# ATmega32u4_Example.net
KiCad netlist of a schematic drawn in EAGLE
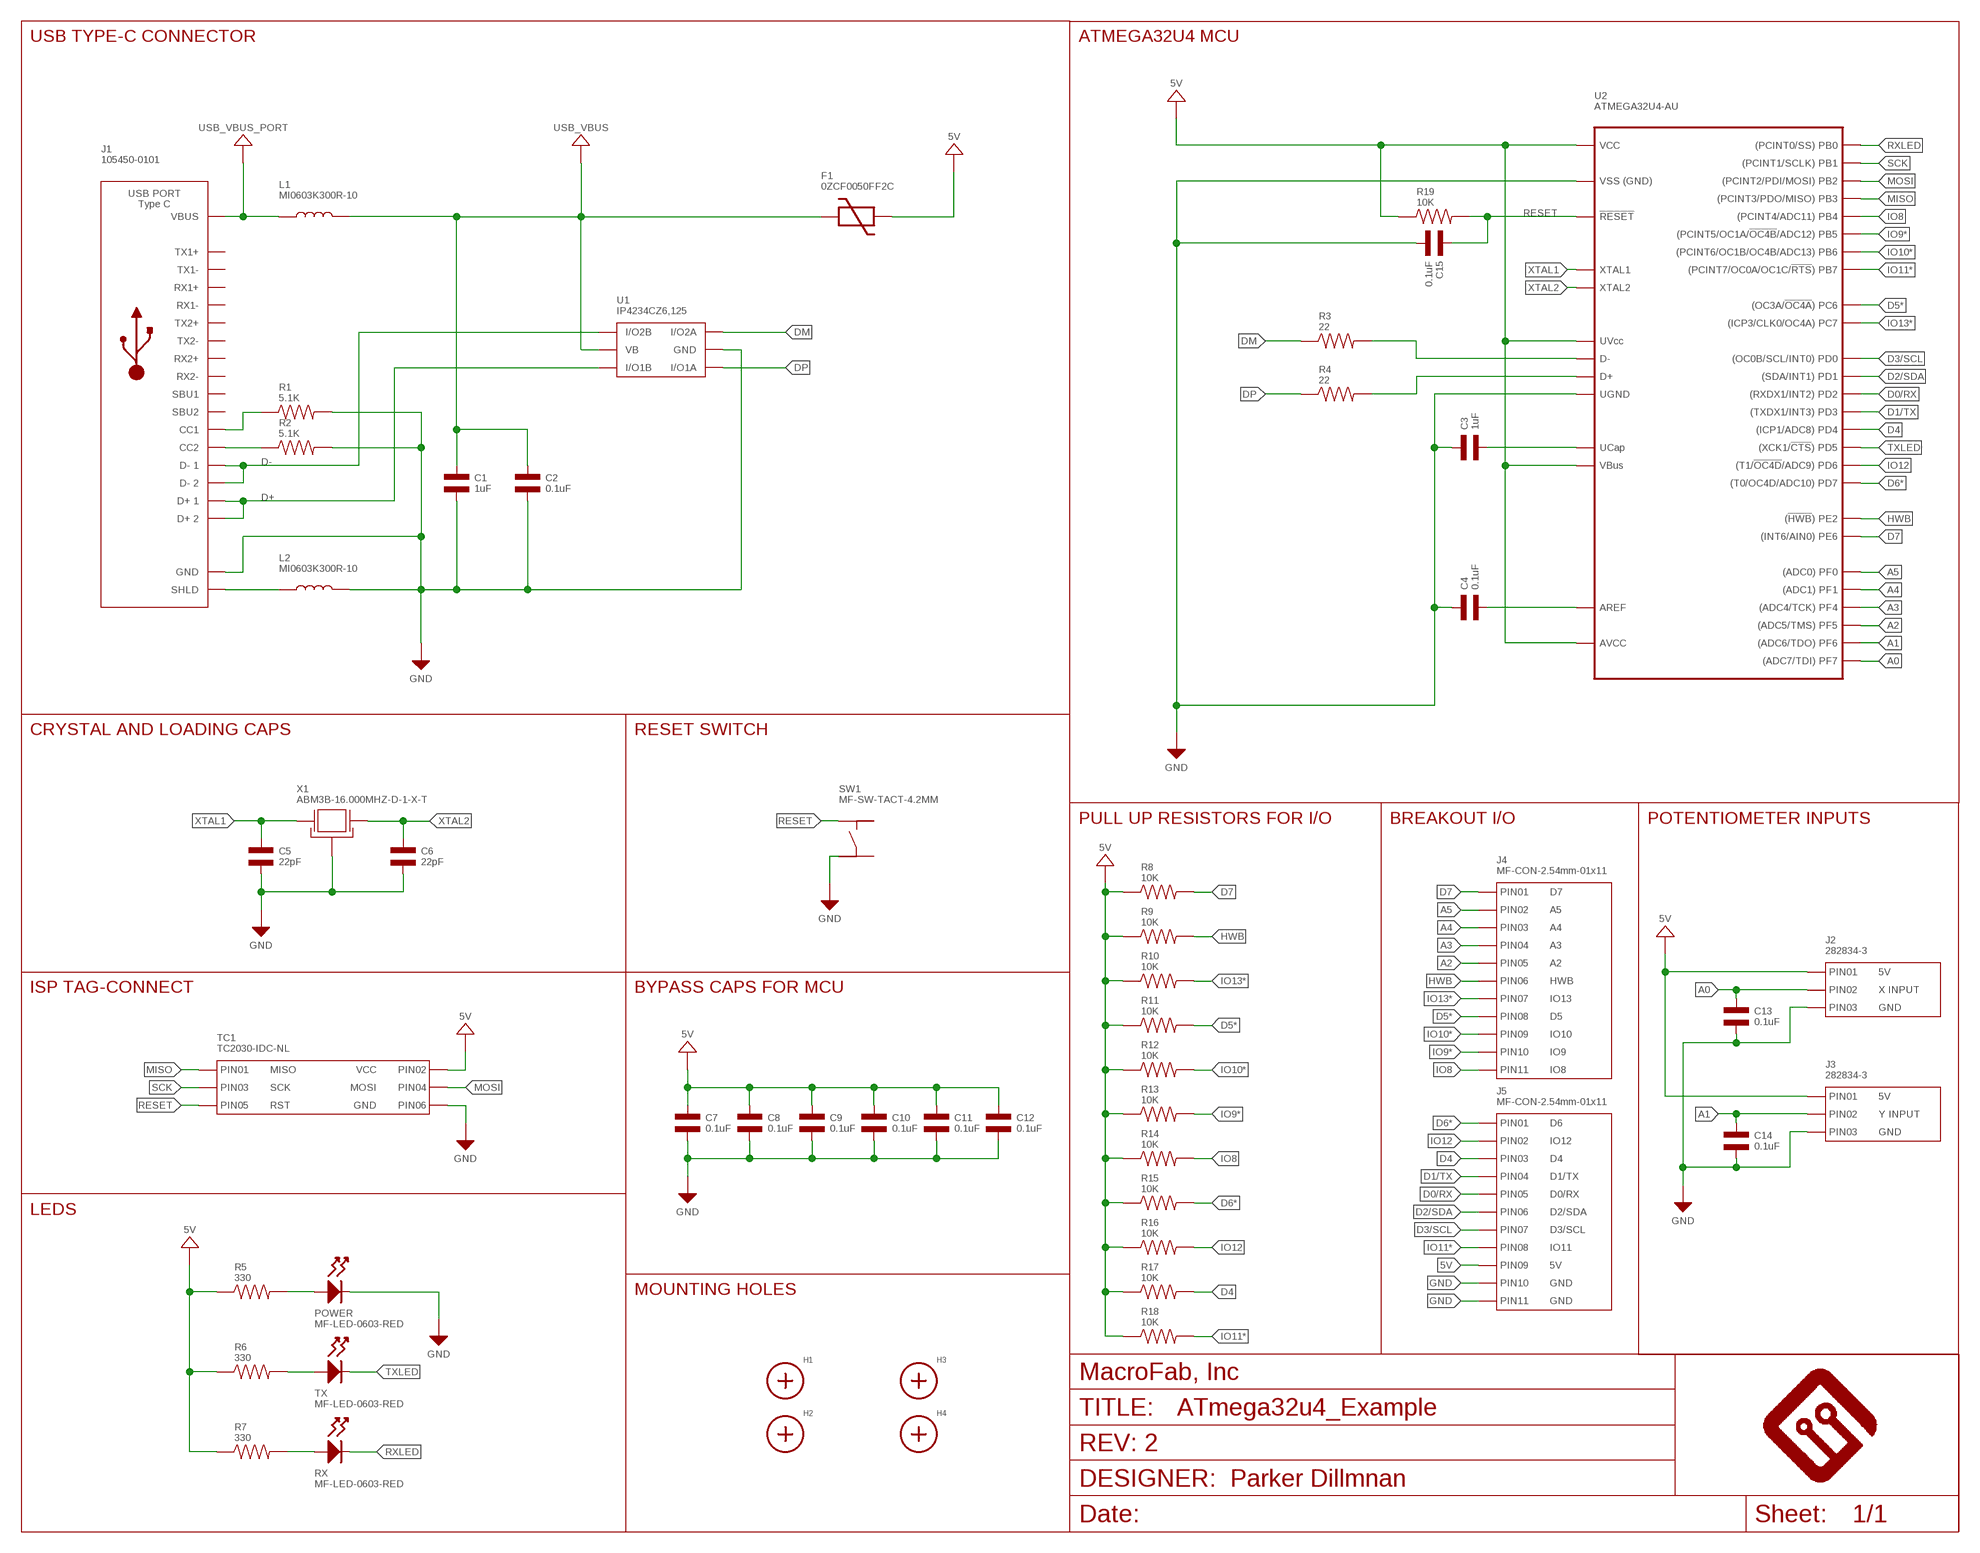
[diagram p0: schematic, sheet 1]

(export (version "E")
  (design (tool "Eeschema 10.0.6"))
  (components
    (comp (ref "C1")
      (value "1uF")
      (footprint "eagle-import:C0603")
      (fields (field (name "MPN") "MF-CAP-0603-1uF"))
      (libsource (lib "eagle-import") (part "CAPACITOR_NP_0603"))
    )
    (comp (ref "C2")
      (value "0.1uF")
      (footprint "eagle-import:C0603")
      (fields (field (name "MPN") "MF-CAP-0603-0.1uF"))
      (libsource (lib "eagle-import") (part "CAPACITOR_NP_0603"))
    )
    (comp (ref "C3")
      (value "1uF")
      (footprint "eagle-import:C0603")
      (fields (field (name "MPN") "MF-CAP-0603-1uF"))
      (libsource (lib "eagle-import") (part "CAPACITOR_NP_0603"))
    )
    (comp (ref "C4")
      (value "0.1uF")
      (footprint "eagle-import:C0603")
      (fields (field (name "MPN") "MF-CAP-0603-0.1uF"))
      (libsource (lib "eagle-import") (part "CAPACITOR_NP_0603"))
    )
    (comp (ref "C5")
      (value "22pF")
      (footprint "eagle-import:C0603")
      (fields (field (name "MPN") "MF-CAP-0603-22pF "))
      (libsource (lib "eagle-import") (part "CAPACITOR_NP_0603"))
    )
    (comp (ref "C6")
      (value "22pF")
      (footprint "eagle-import:C0603")
      (fields (field (name "MPN") "MF-CAP-0603-22pF "))
      (libsource (lib "eagle-import") (part "CAPACITOR_NP_0603"))
    )
    (comp (ref "C7")
      (value "0.1uF")
      (footprint "eagle-import:C0603")
      (fields (field (name "MPN") "MF-CAP-0603-0.1uF"))
      (libsource (lib "eagle-import") (part "CAPACITOR_NP_0603"))
    )
    (comp (ref "C8")
      (value "0.1uF")
      (footprint "eagle-import:C0603")
      (fields (field (name "MPN") "MF-CAP-0603-0.1uF"))
      (libsource (lib "eagle-import") (part "CAPACITOR_NP_0603"))
    )
    (comp (ref "C9")
      (value "0.1uF")
      (footprint "eagle-import:C0603")
      (fields (field (name "MPN") "MF-CAP-0603-0.1uF"))
      (libsource (lib "eagle-import") (part "CAPACITOR_NP_0603"))
    )
    (comp (ref "C10")
      (value "0.1uF")
      (footprint "eagle-import:C0603")
      (fields (field (name "MPN") "MF-CAP-0603-0.1uF"))
      (libsource (lib "eagle-import") (part "CAPACITOR_NP_0603"))
    )
    (comp (ref "C11")
      (value "0.1uF")
      (footprint "eagle-import:C0603")
      (fields (field (name "MPN") "MF-CAP-0603-0.1uF"))
      (libsource (lib "eagle-import") (part "CAPACITOR_NP_0603"))
    )
    (comp (ref "C12")
      (value "0.1uF")
      (footprint "eagle-import:C0603")
      (fields (field (name "MPN") "MF-CAP-0603-0.1uF"))
      (libsource (lib "eagle-import") (part "CAPACITOR_NP_0603"))
    )
    (comp (ref "C13")
      (value "0.1uF")
      (footprint "eagle-import:C0603")
      (fields (field (name "MPN") "MF-CAP-0603-0.1uF"))
      (libsource (lib "eagle-import") (part "CAPACITOR_NP_0603"))
    )
    (comp (ref "C14")
      (value "0.1uF")
      (footprint "eagle-import:C0603")
      (fields (field (name "MPN") "MF-CAP-0603-0.1uF"))
      (libsource (lib "eagle-import") (part "CAPACITOR_NP_0603"))
    )
    (comp (ref "C15")
      (value "0.1uF")
      (footprint "eagle-import:C0603")
      (fields (field (name "MPN") "MF-CAP-0603-0.1uF"))
      (libsource (lib "eagle-import") (part "CAPACITOR_NP_0603"))
    )
    (comp (ref "F1")
      (value "0ZCF0050FF2C")
      (footprint "eagle-import:2920")
      (fields (field (name "MPN") "0ZCF0050FF2C "))
      (libsource (lib "eagle-import") (part "PTC_FUSE_2920"))
    )
    (comp (ref "FRAME1")
      (value "MF_FRAMEDEFAULT")
      (footprint "eagle-import:MF_FRAME_DEFAULT")
      (fields
        (field (name "REVNUM") "REV: N/A")
        (field (name "DNAME") "N/A")
        (field (name "HOUSEPART") "0")
        (field (name "DNAME_1") "Parker Dillmnan")
        (field (name "REVNUM_1") "REV: 2")
      )
      (libsource (lib "eagle-import") (part "MF_FRAMEDEFAULT"))
    )
    (comp (ref "H1")
      (value "MOUNT_HOLE150MIL")
      (footprint "eagle-import:MOUNT_HOLE_150MIL")
      (fields (field (name "POPULATE") "0"))
      (libsource (lib "eagle-import") (part "MOUNT_HOLE150MIL"))
    )
    (comp (ref "H2")
      (value "MOUNT_HOLE150MIL")
      (footprint "eagle-import:MOUNT_HOLE_150MIL")
      (fields (field (name "POPULATE") "0"))
      (libsource (lib "eagle-import") (part "MOUNT_HOLE150MIL"))
    )
    (comp (ref "H3")
      (value "MOUNT_HOLE150MIL")
      (footprint "eagle-import:MOUNT_HOLE_150MIL")
      (fields (field (name "POPULATE") "0"))
      (libsource (lib "eagle-import") (part "MOUNT_HOLE150MIL"))
    )
    (comp (ref "H4")
      (value "MOUNT_HOLE150MIL")
      (footprint "eagle-import:MOUNT_HOLE_150MIL")
      (fields (field (name "POPULATE") "0"))
      (libsource (lib "eagle-import") (part "MOUNT_HOLE150MIL"))
    )
    (comp (ref "J1")
      (value "105450-0101")
      (footprint "eagle-import:105450-0101")
      (fields (field (name "MPN") "105450-0101"))
      (libsource (lib "eagle-import") (part "USB_TYPE-C_105450-0101"))
    )
    (comp (ref "J2")
      (value "282834-3")
      (footprint "eagle-import:282834-3")
      (fields (field (name "LABEL01") "5V") (field (name "LABEL02") "X INPUT") (field (name "LABEL03") "GND"))
      (libsource (lib "eagle-import") (part "CON_01X03_282834-3"))
    )
    (comp (ref "J3")
      (value "282834-3")
      (footprint "eagle-import:282834-3")
      (fields (field (name "LABEL01") "5V") (field (name "LABEL02") "Y INPUT") (field (name "LABEL03") "GND"))
      (libsource (lib "eagle-import") (part "CON_01X03_282834-3"))
    )
    (comp (ref "J4")
      (value "MF-CON-2.54mm-01x11")
      (footprint "eagle-import:PTH_2.54MM_01X11")
      (fields
        (field (name "HOUSEPART") "YES")
        (field (name "LABEL01") "D7")
        (field (name "LABEL02") "A5")
        (field (name "LABEL03") "A4")
        (field (name "LABEL04") "A3")
        (field (name "LABEL05") "A2")
        (field (name "LABEL06") "HWB")
        (field (name "LABEL07") "IO13")
        (field (name "LABEL08") "D5")
        (field (name "LABEL09") "IO10")
        (field (name "LABEL10") "IO9")
        (field (name "LABEL11") "IO8")
      )
      (libsource (lib "eagle-import") (part "CON_01X11_PTH_2.54MM"))
    )
    (comp (ref "J5")
      (value "MF-CON-2.54mm-01x11")
      (footprint "eagle-import:PTH_2.54MM_01X11")
      (fields
        (field (name "HOUSEPART") "YES")
        (field (name "LABEL01") "D6")
        (field (name "LABEL02") "IO12")
        (field (name "LABEL03") "D4")
        (field (name "LABEL04") "D1/TX")
        (field (name "LABEL05") "D0/RX")
        (field (name "LABEL06") "D2/SDA")
        (field (name "LABEL07") "D3/SCL")
        (field (name "LABEL08") "IO11")
        (field (name "LABEL09") "5V")
        (field (name "LABEL10") "GND")
        (field (name "LABEL11") "GND")
      )
      (libsource (lib "eagle-import") (part "CON_01X11_PTH_2.54MM"))
    )
    (comp (ref "L1")
      (value "MI0603K300R-10")
      (footprint "eagle-import:L0603")
      (fields (field (name "MPN") "MI0603K300R-10"))
      (libsource (lib "eagle-import") (part "INDUCTOR_0603"))
    )
    (comp (ref "L2")
      (value "MI0603K300R-10")
      (footprint "eagle-import:L0603")
      (fields (field (name "MPN") "MI0603K300R-10"))
      (libsource (lib "eagle-import") (part "INDUCTOR_0603"))
    )
    (comp (ref "POWER")
      (value "MF-LED-0603-RED")
      (footprint "eagle-import:LED0603")
      (fields (field (name "HOUSEPART") "YES"))
      (libsource (lib "eagle-import") (part "LED_SINGLE-0603-RED"))
    )
    (comp (ref "R1")
      (value "5.1K")
      (footprint "eagle-import:R0603")
      (fields (field (name "MPN") "ERJ-3EKF5101V"))
      (libsource (lib "eagle-import") (part "RESISTOR_0603"))
    )
    (comp (ref "R2")
      (value "5.1K")
      (footprint "eagle-import:R0603")
      (fields (field (name "MPN") "ERJ-3EKF5101V"))
      (libsource (lib "eagle-import") (part "RESISTOR_0603"))
    )
    (comp (ref "R3")
      (value "22")
      (footprint "eagle-import:R0603")
      (fields (field (name "MPN") "MF-RES-0603-22"))
      (libsource (lib "eagle-import") (part "RESISTOR_0603"))
    )
    (comp (ref "R4")
      (value "22")
      (footprint "eagle-import:R0603")
      (fields (field (name "MPN") "MF-RES-0603-22"))
      (libsource (lib "eagle-import") (part "RESISTOR_0603"))
    )
    (comp (ref "R5")
      (value "330")
      (footprint "eagle-import:R0603")
      (fields (field (name "MPN") "MF-RES-0603-330"))
      (libsource (lib "eagle-import") (part "RESISTOR_0603"))
    )
    (comp (ref "R6")
      (value "330")
      (footprint "eagle-import:R0603")
      (fields (field (name "MPN") "MF-RES-0603-330"))
      (libsource (lib "eagle-import") (part "RESISTOR_0603"))
    )
    (comp (ref "R7")
      (value "330")
      (footprint "eagle-import:R0603")
      (fields (field (name "MPN") "MF-RES-0603-330"))
      (libsource (lib "eagle-import") (part "RESISTOR_0603"))
    )
    (comp (ref "R8")
      (value "10K")
      (footprint "eagle-import:R0603")
      (fields (field (name "MPN") "MF-RES-0603-10K"))
      (libsource (lib "eagle-import") (part "RESISTOR_0603"))
    )
    (comp (ref "R9")
      (value "10K")
      (footprint "eagle-import:R0603")
      (fields (field (name "MPN") "MF-RES-0603-10K"))
      (libsource (lib "eagle-import") (part "RESISTOR_0603"))
    )
    (comp (ref "R10")
      (value "10K")
      (footprint "eagle-import:R0603")
      (fields (field (name "MPN") "MF-RES-0603-10K"))
      (libsource (lib "eagle-import") (part "RESISTOR_0603"))
    )
    (comp (ref "R11")
      (value "10K")
      (footprint "eagle-import:R0603")
      (fields (field (name "MPN") "MF-RES-0603-10K"))
      (libsource (lib "eagle-import") (part "RESISTOR_0603"))
    )
    (comp (ref "R12")
      (value "10K")
      (footprint "eagle-import:R0603")
      (fields (field (name "MPN") "MF-RES-0603-10K"))
      (libsource (lib "eagle-import") (part "RESISTOR_0603"))
    )
    (comp (ref "R13")
      (value "10K")
      (footprint "eagle-import:R0603")
      (fields (field (name "MPN") "MF-RES-0603-10K"))
      (libsource (lib "eagle-import") (part "RESISTOR_0603"))
    )
    (comp (ref "R14")
      (value "10K")
      (footprint "eagle-import:R0603")
      (fields (field (name "MPN") "MF-RES-0603-10K"))
      (libsource (lib "eagle-import") (part "RESISTOR_0603"))
    )
    (comp (ref "R15")
      (value "10K")
      (footprint "eagle-import:R0603")
      (fields (field (name "MPN") "MF-RES-0603-10K"))
      (libsource (lib "eagle-import") (part "RESISTOR_0603"))
    )
    (comp (ref "R16")
      (value "10K")
      (footprint "eagle-import:R0603")
      (fields (field (name "MPN") "MF-RES-0603-10K"))
      (libsource (lib "eagle-import") (part "RESISTOR_0603"))
    )
    (comp (ref "R17")
      (value "10K")
      (footprint "eagle-import:R0603")
      (fields (field (name "MPN") "MF-RES-0603-10K"))
      (libsource (lib "eagle-import") (part "RESISTOR_0603"))
    )
    (comp (ref "R18")
      (value "10K")
      (footprint "eagle-import:R0603")
      (fields (field (name "MPN") "MF-RES-0603-10K"))
      (libsource (lib "eagle-import") (part "RESISTOR_0603"))
    )
    (comp (ref "R19")
      (value "10K")
      (footprint "eagle-import:R0603")
      (fields (field (name "MPN") "MF-RES-0603-10K"))
      (libsource (lib "eagle-import") (part "RESISTOR_0603"))
    )
    (comp (ref "RX")
      (value "MF-LED-0603-RED")
      (footprint "eagle-import:LED0603")
      (fields (field (name "HOUSEPART") "YES"))
      (libsource (lib "eagle-import") (part "LED_SINGLE-0603-RED"))
    )
    (comp (ref "SW1")
      (value "MF-SW-TACT-4.2MM")
      (footprint "eagle-import:TACT4.2MM")
      (fields (field (name "HOUSEPART") "YES"))
      (libsource (lib "eagle-import") (part "TACT_4.2MM"))
    )
    (comp (ref "TC1")
      (value "TC2030-IDC-NL")
      (footprint "eagle-import:TC2030-IDC-NL")
      (fields
        (field (name "HOUSEPART") "NO")
        (field (name "LABEL01") "MISO")
        (field (name "LABEL02") "VCC")
        (field (name "LABEL03") "SCK")
        (field (name "LABEL04") "MOSI")
        (field (name "LABEL05") "RST")
        (field (name "LABEL06") "GND")
      )
      (libsource (lib "eagle-import") (part "CON_02X03_TC2030-IDC-NL_AVRISP"))
    )
    (comp (ref "TX")
      (value "MF-LED-0603-RED")
      (footprint "eagle-import:LED0603")
      (fields (field (name "HOUSEPART") "YES"))
      (libsource (lib "eagle-import") (part "LED_SINGLE-0603-RED"))
    )
    (comp (ref "U1")
      (value "IP4234CZ6,125")
      (footprint "eagle-import:IP4234CZ6_SOT-457-6")
      (libsource (lib "eagle-import") (part "IP4234CZ6"))
    )
    (comp (ref "U2")
      (value "ATMEGA32U4-AU")
      (footprint "eagle-import:TQFP44")
      (fields (field (name "HOUSEPART") "NO"))
      (libsource (lib "eagle-import") (part "ATMEGA32U4-AU"))
    )
    (comp (ref "X1")
      (value "ABM3B-16.000MHZ-D-1-X-T")
      (footprint "eagle-import:5MMX3.2MM")
      (fields (field (name "HOUSEPART") "NO") (field (name "MPN") "ABM3B-16.000MHZ-D-1-X-T"))
      (libsource (lib "eagle-import") (part "CYRSTAL_GND_ABM3B"))
    )
  )
  (nets
    (net (code "1") (name "/D+") (class "Default")
      (node (ref "J1") (pin "A6") (pinfunction "D+1_A6") (pintype "bidirectional"))
      (node (ref "J1") (pin "B6") (pinfunction "D+2_B6") (pintype "bidirectional"))
      (node (ref "U1") (pin "3") (pinfunction "I/O1B_3") (pintype "bidirectional"))
    )
    (net (code "2") (name "/D-") (class "Default")
      (node (ref "J1") (pin "A7") (pinfunction "D-1_A7") (pintype "bidirectional"))
      (node (ref "J1") (pin "B7") (pinfunction "D-2_B7") (pintype "bidirectional"))
      (node (ref "U1") (pin "4") (pinfunction "I/O2B_4") (pintype "bidirectional"))
    )
    (net (code "3") (name "5V") (class "Default")
      (node (ref "C10") (pin "P$1") (pinfunction "P$1_P$1") (pintype "passive"))
      (node (ref "C11") (pin "P$1") (pinfunction "P$1_P$1") (pintype "passive"))
      (node (ref "C12") (pin "P$1") (pinfunction "P$1_P$1") (pintype "passive"))
      (node (ref "C7") (pin "P$1") (pinfunction "P$1_P$1") (pintype "passive"))
      (node (ref "C8") (pin "P$1") (pinfunction "P$1_P$1") (pintype "passive"))
      (node (ref "C9") (pin "P$1") (pinfunction "P$1_P$1") (pintype "passive"))
      (node (ref "F1") (pin "2") (pinfunction "P$2_2") (pintype "bidirectional"))
      (node (ref "J2") (pin "P$1") (pinfunction "PIN1_P$1") (pintype "bidirectional"))
      (node (ref "J3") (pin "P$1") (pinfunction "PIN1_P$1") (pintype "bidirectional"))
      (node (ref "J5") (pin "P$9") (pinfunction "PIN9_P$9") (pintype "bidirectional"))
      (node (ref "R10") (pin "P$1") (pinfunction "P$1_P$1") (pintype "passive"))
      (node (ref "R11") (pin "P$1") (pinfunction "P$1_P$1") (pintype "passive"))
      (node (ref "R12") (pin "P$1") (pinfunction "P$1_P$1") (pintype "passive"))
      (node (ref "R13") (pin "P$1") (pinfunction "P$1_P$1") (pintype "passive"))
      (node (ref "R14") (pin "P$1") (pinfunction "P$1_P$1") (pintype "passive"))
      (node (ref "R15") (pin "P$1") (pinfunction "P$1_P$1") (pintype "passive"))
      (node (ref "R16") (pin "P$1") (pinfunction "P$1_P$1") (pintype "passive"))
      (node (ref "R17") (pin "P$1") (pinfunction "P$1_P$1") (pintype "passive"))
      (node (ref "R18") (pin "P$1") (pinfunction "P$1_P$1") (pintype "passive"))
      (node (ref "R19") (pin "P$1") (pinfunction "P$1_P$1") (pintype "passive"))
      (node (ref "R5") (pin "P$1") (pinfunction "P$1_P$1") (pintype "passive"))
      (node (ref "R6") (pin "P$1") (pinfunction "P$1_P$1") (pintype "passive"))
      (node (ref "R7") (pin "P$1") (pinfunction "P$1_P$1") (pintype "passive"))
      (node (ref "R8") (pin "P$1") (pinfunction "P$1_P$1") (pintype "passive"))
      (node (ref "R9") (pin "P$1") (pinfunction "P$1_P$1") (pintype "passive"))
      (node (ref "TC1") (pin "P$2") (pinfunction "PIN2_P$2") (pintype "bidirectional"))
      (node (ref "U2") (pin "P$14") (pinfunction "VCC_P$14") (pintype "power_in"))
      (node (ref "U2") (pin "P$2") (pinfunction "UVCC_P$2") (pintype "power_in"))
      (node (ref "U2") (pin "P$24") (pinfunction "AVCC_P$24") (pintype "power_in"))
      (node (ref "U2") (pin "P$34") (pinfunction "VCC_P$34") (pintype "power_in"))
      (node (ref "U2") (pin "P$44") (pinfunction "AVCC_P$44") (pintype "power_in"))
      (node (ref "U2") (pin "P$7") (pinfunction "VBUS_P$7") (pintype "power_in"))
    )
    (net (code "4") (name "A0") (class "Default")
      (node (ref "C13") (pin "P$1") (pinfunction "P$1_P$1") (pintype "passive"))
      (node (ref "J2") (pin "P$2") (pinfunction "PIN2_P$2") (pintype "bidirectional"))
      (node (ref "U2") (pin "P$36") (pinfunction "PF7_P$36") (pintype "bidirectional"))
    )
    (net (code "5") (name "A1") (class "Default")
      (node (ref "C14") (pin "P$1") (pinfunction "P$1_P$1") (pintype "passive"))
      (node (ref "J3") (pin "P$2") (pinfunction "PIN2_P$2") (pintype "bidirectional"))
      (node (ref "U2") (pin "P$37") (pinfunction "PF6_P$37") (pintype "bidirectional"))
    )
    (net (code "6") (name "A2") (class "Default")
      (node (ref "J4") (pin "P$5") (pinfunction "PIN5_P$5") (pintype "bidirectional"))
      (node (ref "U2") (pin "P$38") (pinfunction "PF5_P$38") (pintype "bidirectional"))
    )
    (net (code "7") (name "A3") (class "Default")
      (node (ref "J4") (pin "P$4") (pinfunction "PIN4_P$4") (pintype "bidirectional"))
      (node (ref "U2") (pin "P$39") (pinfunction "PF4_P$39") (pintype "bidirectional"))
    )
    (net (code "8") (name "A4") (class "Default")
      (node (ref "J4") (pin "P$3") (pinfunction "PIN3_P$3") (pintype "bidirectional"))
      (node (ref "U2") (pin "P$40") (pinfunction "PF1_P$40") (pintype "bidirectional"))
    )
    (net (code "9") (name "A5") (class "Default")
      (node (ref "J4") (pin "P$2") (pinfunction "PIN2_P$2") (pintype "bidirectional"))
      (node (ref "U2") (pin "P$41") (pinfunction "PF0_P$41") (pintype "bidirectional"))
    )
    (net (code "10") (name "D0{slash}RX") (class "Default")
      (node (ref "J5") (pin "P$5") (pinfunction "PIN5_P$5") (pintype "bidirectional"))
      (node (ref "U2") (pin "P$20") (pinfunction "PD2_P$20") (pintype "bidirectional"))
    )
    (net (code "11") (name "D1{slash}TX") (class "Default")
      (node (ref "J5") (pin "P$4") (pinfunction "PIN4_P$4") (pintype "bidirectional"))
      (node (ref "U2") (pin "P$21") (pinfunction "PD3_P$21") (pintype "bidirectional"))
    )
    (net (code "12") (name "D2{slash}SDA") (class "Default")
      (node (ref "J5") (pin "P$6") (pinfunction "PIN6_P$6") (pintype "bidirectional"))
      (node (ref "U2") (pin "P$19") (pinfunction "PD1_P$19") (pintype "bidirectional"))
    )
    (net (code "13") (name "D3{slash}SCL") (class "Default")
      (node (ref "J5") (pin "P$7") (pinfunction "PIN7_P$7") (pintype "bidirectional"))
      (node (ref "U2") (pin "P$18") (pinfunction "PD0_P$18") (pintype "bidirectional"))
    )
    (net (code "14") (name "D4") (class "Default")
      (node (ref "J5") (pin "P$3") (pinfunction "PIN3_P$3") (pintype "bidirectional"))
      (node (ref "R17") (pin "P$2") (pinfunction "P$2_P$2") (pintype "passive"))
      (node (ref "U2") (pin "P$25") (pinfunction "PD4_P$25") (pintype "bidirectional"))
    )
    (net (code "15") (name "D5*") (class "Default")
      (node (ref "J4") (pin "P$8") (pinfunction "PIN8_P$8") (pintype "bidirectional"))
      (node (ref "R11") (pin "P$2") (pinfunction "P$2_P$2") (pintype "passive"))
      (node (ref "U2") (pin "P$31") (pinfunction "PC6_P$31") (pintype "bidirectional"))
    )
    (net (code "16") (name "D6*") (class "Default")
      (node (ref "J5") (pin "P$1") (pinfunction "PIN1_P$1") (pintype "bidirectional"))
      (node (ref "R15") (pin "P$2") (pinfunction "P$2_P$2") (pintype "passive"))
      (node (ref "U2") (pin "P$27") (pinfunction "PD7_P$27") (pintype "bidirectional"))
    )
    (net (code "17") (name "D7") (class "Default")
      (node (ref "J4") (pin "P$1") (pinfunction "PIN1_P$1") (pintype "bidirectional"))
      (node (ref "R8") (pin "P$2") (pinfunction "P$2_P$2") (pintype "passive"))
      (node (ref "U2") (pin "P$1") (pinfunction "PE6_P$1") (pintype "bidirectional"))
    )
    (net (code "18") (name "DM") (class "Default")
      (node (ref "R3") (pin "P$1") (pinfunction "P$1_P$1") (pintype "passive"))
      (node (ref "U1") (pin "6") (pinfunction "I/O2A_6") (pintype "bidirectional"))
    )
    (net (code "19") (name "DP") (class "Default")
      (node (ref "R4") (pin "P$1") (pinfunction "P$1_P$1") (pintype "passive"))
      (node (ref "U1") (pin "1") (pinfunction "I/O1A_1") (pintype "bidirectional"))
    )
    (net (code "20") (name "GND") (class "Default")
      (node (ref "C1") (pin "P$2") (pinfunction "P$2_P$2") (pintype "passive"))
      (node (ref "C10") (pin "P$2") (pinfunction "P$2_P$2") (pintype "passive"))
      (node (ref "C11") (pin "P$2") (pinfunction "P$2_P$2") (pintype "passive"))
      (node (ref "C12") (pin "P$2") (pinfunction "P$2_P$2") (pintype "passive"))
      (node (ref "C13") (pin "P$2") (pinfunction "P$2_P$2") (pintype "passive"))
      (node (ref "C14") (pin "P$2") (pinfunction "P$2_P$2") (pintype "passive"))
      (node (ref "C15") (pin "P$2") (pinfunction "P$2_P$2") (pintype "passive"))
      (node (ref "C2") (pin "P$2") (pinfunction "P$2_P$2") (pintype "passive"))
      (node (ref "C3") (pin "P$1") (pinfunction "P$1_P$1") (pintype "passive"))
      (node (ref "C4") (pin "P$1") (pinfunction "P$1_P$1") (pintype "passive"))
      (node (ref "C5") (pin "P$2") (pinfunction "P$2_P$2") (pintype "passive"))
      (node (ref "C6") (pin "P$2") (pinfunction "P$2_P$2") (pintype "passive"))
      (node (ref "C7") (pin "P$2") (pinfunction "P$2_P$2") (pintype "passive"))
      (node (ref "C8") (pin "P$2") (pinfunction "P$2_P$2") (pintype "passive"))
      (node (ref "C9") (pin "P$2") (pinfunction "P$2_P$2") (pintype "passive"))
      (node (ref "J1") (pin "A1") (pinfunction "GND_A1") (pintype "bidirectional"))
      (node (ref "J1") (pin "A12") (pinfunction "GND_A12") (pintype "bidirectional"))
      (node (ref "J1") (pin "B1") (pinfunction "GND_B1") (pintype "bidirectional"))
      (node (ref "J1") (pin "B12") (pinfunction "GND_B12") (pintype "bidirectional"))
      (node (ref "J2") (pin "P$3") (pinfunction "PIN3_P$3") (pintype "bidirectional"))
      (node (ref "J3") (pin "P$3") (pinfunction "PIN3_P$3") (pintype "bidirectional"))
      (node (ref "J5") (pin "P$10") (pinfunction "PIN10_P$10") (pintype "bidirectional"))
      (node (ref "J5") (pin "P$11") (pinfunction "PIN11_P$11") (pintype "bidirectional"))
      (node (ref "L2") (pin "P$2") (pinfunction "P$2_P$2") (pintype "passive"))
      (node (ref "POWER") (pin "CATHODE") (pinfunction "CATHODE_CATHODE") (pintype "power_in"))
      (node (ref "R1") (pin "P$2") (pinfunction "P$2_P$2") (pintype "passive"))
      (node (ref "R2") (pin "P$2") (pinfunction "P$2_P$2") (pintype "passive"))
      (node (ref "SW1") (pin "P$3") (pinfunction "P$3_P$3") (pintype "bidirectional"))
      (node (ref "TC1") (pin "P$6") (pinfunction "PIN6_P$6") (pintype "bidirectional"))
      (node (ref "U1") (pin "2") (pinfunction "GND_2") (pintype "bidirectional"))
      (node (ref "U2") (pin "P$15") (pinfunction "GND_P$15") (pintype "power_in"))
      (node (ref "U2") (pin "P$23") (pinfunction "GND_P$23") (pintype "power_in"))
      (node (ref "U2") (pin "P$35") (pinfunction "GND_P$35") (pintype "power_in"))
      (node (ref "U2") (pin "P$43") (pinfunction "GND_P$43") (pintype "power_in"))
      (node (ref "U2") (pin "P$5") (pinfunction "UGND_P$5") (pintype "power_in"))
      (node (ref "X1") (pin "P$2") (pinfunction "GND_P$2") (pintype "bidirectional"))
      (node (ref "X1") (pin "P$4") (pinfunction "GND_P$4") (pintype "bidirectional"))
    )
    (net (code "21") (name "HWB") (class "Default")
      (node (ref "J4") (pin "P$6") (pinfunction "PIN6_P$6") (pintype "bidirectional"))
      (node (ref "R9") (pin "P$2") (pinfunction "P$2_P$2") (pintype "passive"))
      (node (ref "U2") (pin "P$33") (pinfunction "PE2_P$33") (pintype "bidirectional"))
    )
    (net (code "22") (name "IO8") (class "Default")
      (node (ref "J4") (pin "P$11") (pinfunction "PIN11_P$11") (pintype "bidirectional"))
      (node (ref "R14") (pin "P$2") (pinfunction "P$2_P$2") (pintype "passive"))
      (node (ref "U2") (pin "P$28") (pinfunction "PB4_P$28") (pintype "bidirectional"))
    )
    (net (code "23") (name "IO9*") (class "Default")
      (node (ref "J4") (pin "P$10") (pinfunction "PIN10_P$10") (pintype "bidirectional"))
      (node (ref "R13") (pin "P$2") (pinfunction "P$2_P$2") (pintype "passive"))
      (node (ref "U2") (pin "P$29") (pinfunction "PB5_P$29") (pintype "bidirectional"))
    )
    (net (code "24") (name "IO10*") (class "Default")
      (node (ref "J4") (pin "P$9") (pinfunction "PIN9_P$9") (pintype "bidirectional"))
      (node (ref "R12") (pin "P$2") (pinfunction "P$2_P$2") (pintype "passive"))
      (node (ref "U2") (pin "P$30") (pinfunction "PB6_P$30") (pintype "bidirectional"))
    )
    (net (code "25") (name "IO11*") (class "Default")
      (node (ref "J5") (pin "P$8") (pinfunction "PIN8_P$8") (pintype "bidirectional"))
      (node (ref "R18") (pin "P$2") (pinfunction "P$2_P$2") (pintype "passive"))
      (node (ref "U2") (pin "P$12") (pinfunction "PB7_P$12") (pintype "bidirectional"))
    )
    (net (code "26") (name "IO12") (class "Default")
      (node (ref "J5") (pin "P$2") (pinfunction "PIN2_P$2") (pintype "bidirectional"))
      (node (ref "R16") (pin "P$2") (pinfunction "P$2_P$2") (pintype "passive"))
      (node (ref "U2") (pin "P$26") (pinfunction "PD6_P$26") (pintype "bidirectional"))
    )
    (net (code "27") (name "IO13*") (class "Default")
      (node (ref "J4") (pin "P$7") (pinfunction "PIN7_P$7") (pintype "bidirectional"))
      (node (ref "R10") (pin "P$2") (pinfunction "P$2_P$2") (pintype "passive"))
      (node (ref "U2") (pin "P$32") (pinfunction "PC7_P$32") (pintype "bidirectional"))
    )
    (net (code "28") (name "MISO") (class "Default")
      (node (ref "TC1") (pin "P$1") (pinfunction "PIN1_P$1") (pintype "bidirectional"))
      (node (ref "U2") (pin "P$11") (pinfunction "PB3_P$11") (pintype "bidirectional"))
    )
    (net (code "29") (name "MOSI") (class "Default")
      (node (ref "TC1") (pin "P$4") (pinfunction "PIN4_P$4") (pintype "bidirectional"))
      (node (ref "U2") (pin "P$10") (pinfunction "PB2_P$10") (pintype "bidirectional"))
    )
    (net (code "30") (name "Net-(J1-CC1)") (class "Default")
      (node (ref "J1") (pin "A5") (pinfunction "CC1_A5") (pintype "bidirectional"))
      (node (ref "R1") (pin "P$1") (pinfunction "P$1_P$1") (pintype "passive"))
    )
    (net (code "31") (name "Net-(J1-CC2)") (class "Default")
      (node (ref "J1") (pin "B5") (pinfunction "CC2_B5") (pintype "bidirectional"))
      (node (ref "R2") (pin "P$1") (pinfunction "P$1_P$1") (pintype "passive"))
    )
    (net (code "32") (name "Net-(J1-SHLD-PadS_T1)") (class "Default")
      (node (ref "J1") (pin "S_T1") (pinfunction "SHLD_S_T1") (pintype "bidirectional"))
      (node (ref "J1") (pin "S_T2") (pinfunction "SHLD_S_T2") (pintype "bidirectional"))
      (node (ref "J1") (pin "S_T3") (pinfunction "SHLD_S_T3") (pintype "bidirectional"))
      (node (ref "J1") (pin "S_T4") (pinfunction "SHLD_S_T4") (pintype "bidirectional"))
      (node (ref "L2") (pin "P$1") (pinfunction "P$1_P$1") (pintype "passive"))
    )
    (net (code "33") (name "Net-(POWER-PadANODE)") (class "Default")
      (node (ref "POWER") (pin "ANODE") (pinfunction "ANODE_ANODE") (pintype "power_in"))
      (node (ref "R5") (pin "P$2") (pinfunction "P$2_P$2") (pintype "passive"))
    )
    (net (code "34") (name "Net-(R6-PadP$2)") (class "Default")
      (node (ref "R6") (pin "P$2") (pinfunction "P$2_P$2") (pintype "passive"))
      (node (ref "TX") (pin "ANODE") (pinfunction "ANODE_ANODE") (pintype "power_in"))
    )
    (net (code "35") (name "Net-(R7-PadP$2)") (class "Default")
      (node (ref "R7") (pin "P$2") (pinfunction "P$2_P$2") (pintype "passive"))
      (node (ref "RX") (pin "ANODE") (pinfunction "ANODE_ANODE") (pintype "power_in"))
    )
    (net (code "36") (name "Net-(U2-AREF)") (class "Default")
      (node (ref "C4") (pin "P$2") (pinfunction "P$2_P$2") (pintype "passive"))
      (node (ref "U2") (pin "P$42") (pinfunction "AREF_P$42") (pintype "power_in"))
    )
    (net (code "37") (name "Net-(U2-D+)") (class "Default")
      (node (ref "R4") (pin "P$2") (pinfunction "P$2_P$2") (pintype "passive"))
      (node (ref "U2") (pin "P$4") (pinfunction "D+_P$4") (pintype "bidirectional"))
    )
    (net (code "38") (name "Net-(U2-D-)") (class "Default")
      (node (ref "R3") (pin "P$2") (pinfunction "P$2_P$2") (pintype "passive"))
      (node (ref "U2") (pin "P$3") (pinfunction "D-_P$3") (pintype "bidirectional"))
    )
    (net (code "39") (name "Net-(U2-UCAP)") (class "Default")
      (node (ref "C3") (pin "P$2") (pinfunction "P$2_P$2") (pintype "passive"))
      (node (ref "U2") (pin "P$6") (pinfunction "UCAP_P$6") (pintype "power_in"))
    )
    (net (code "40") (name "RESET") (class "Default")
      (node (ref "C15") (pin "P$1") (pinfunction "P$1_P$1") (pintype "passive"))
      (node (ref "R19") (pin "P$2") (pinfunction "P$2_P$2") (pintype "passive"))
      (node (ref "SW1") (pin "P$1") (pinfunction "P$1_P$1") (pintype "bidirectional"))
      (node (ref "TC1") (pin "P$5") (pinfunction "PIN5_P$5") (pintype "bidirectional"))
      (node (ref "U2") (pin "P$13") (pinfunction "~{RESET}_P$13") (pintype "bidirectional"))
    )
    (net (code "41") (name "RXLED") (class "Default")
      (node (ref "RX") (pin "CATHODE") (pinfunction "CATHODE_CATHODE") (pintype "power_in"))
      (node (ref "U2") (pin "P$8") (pinfunction "PB0_P$8") (pintype "bidirectional"))
    )
    (net (code "42") (name "SCK") (class "Default")
      (node (ref "TC1") (pin "P$3") (pinfunction "PIN3_P$3") (pintype "bidirectional"))
      (node (ref "U2") (pin "P$9") (pinfunction "PB1_P$9") (pintype "bidirectional"))
    )
    (net (code "43") (name "TXLED") (class "Default")
      (node (ref "TX") (pin "CATHODE") (pinfunction "CATHODE_CATHODE") (pintype "power_in"))
      (node (ref "U2") (pin "P$22") (pinfunction "PD5_P$22") (pintype "bidirectional"))
    )
    (net (code "44") (name "USB_VBUS") (class "Default")
      (node (ref "C1") (pin "P$1") (pinfunction "P$1_P$1") (pintype "passive"))
      (node (ref "C2") (pin "P$1") (pinfunction "P$1_P$1") (pintype "passive"))
      (node (ref "F1") (pin "1") (pinfunction "P$1_1") (pintype "bidirectional"))
      (node (ref "L1") (pin "P$2") (pinfunction "P$2_P$2") (pintype "passive"))
      (node (ref "U1") (pin "5") (pinfunction "VB_5") (pintype "bidirectional"))
    )
    (net (code "45") (name "USB_VBUS_PORT") (class "Default")
      (node (ref "J1") (pin "A4") (pinfunction "VBUS_A4") (pintype "bidirectional"))
      (node (ref "J1") (pin "A9") (pinfunction "VBUS_A9") (pintype "bidirectional"))
      (node (ref "J1") (pin "B4") (pinfunction "VBUS_B4") (pintype "bidirectional"))
      (node (ref "J1") (pin "B9") (pinfunction "VBUS_B9") (pintype "bidirectional"))
      (node (ref "L1") (pin "P$1") (pinfunction "P$1_P$1") (pintype "passive"))
    )
    (net (code "46") (name "XTAL1") (class "Default")
      (node (ref "C5") (pin "P$1") (pinfunction "P$1_P$1") (pintype "passive"))
      (node (ref "U2") (pin "P$17") (pinfunction "XTAL1_P$17") (pintype "bidirectional"))
      (node (ref "X1") (pin "P$1") (pinfunction "X0_P$1") (pintype "bidirectional"))
    )
    (net (code "47") (name "XTAL2") (class "Default")
      (node (ref "C6") (pin "P$1") (pinfunction "P$1_P$1") (pintype "passive"))
      (node (ref "U2") (pin "P$16") (pinfunction "XTAL2_P$16") (pintype "bidirectional"))
      (node (ref "X1") (pin "P$3") (pinfunction "X1_P$3") (pintype "bidirectional"))
    )
    (net (code "48") (name "unconnected-(J1-RX1+-PadB11)") (class "Default")
      (node (ref "J1") (pin "B11") (pinfunction "RX1+_B11") (pintype "bidirectional"))
    )
    (net (code "49") (name "unconnected-(J1-RX1--PadB10)") (class "Default")
      (node (ref "J1") (pin "B10") (pinfunction "RX1-_B10") (pintype "bidirectional"))
    )
    (net (code "50") (name "unconnected-(J1-RX2+-PadA11)") (class "Default")
      (node (ref "J1") (pin "A11") (pinfunction "RX2+_A11") (pintype "bidirectional"))
    )
    (net (code "51") (name "unconnected-(J1-RX2--PadA10)") (class "Default")
      (node (ref "J1") (pin "A10") (pinfunction "RX2-_A10") (pintype "bidirectional"))
    )
    (net (code "52") (name "unconnected-(J1-SBU1-PadA8)") (class "Default")
      (node (ref "J1") (pin "A8") (pinfunction "SBU1_A8") (pintype "bidirectional"))
    )
    (net (code "53") (name "unconnected-(J1-SBU2-PadB8)") (class "Default")
      (node (ref "J1") (pin "B8") (pinfunction "SBU2_B8") (pintype "bidirectional"))
    )
    (net (code "54") (name "unconnected-(J1-TX1+-PadA2)") (class "Default")
      (node (ref "J1") (pin "A2") (pinfunction "TX1+_A2") (pintype "bidirectional"))
    )
    (net (code "55") (name "unconnected-(J1-TX1--PadA3)") (class "Default")
      (node (ref "J1") (pin "A3") (pinfunction "TX1-_A3") (pintype "bidirectional"))
    )
    (net (code "56") (name "unconnected-(J1-TX2+-PadB2)") (class "Default")
      (node (ref "J1") (pin "B2") (pinfunction "TX2+_B2") (pintype "bidirectional"))
    )
    (net (code "57") (name "unconnected-(J1-TX2--PadB3)") (class "Default")
      (node (ref "J1") (pin "B3") (pinfunction "TX2-_B3") (pintype "bidirectional"))
    )
    (net (code "58") (name "unconnected-(SW1-PadP$2)") (class "Default")
      (node (ref "SW1") (pin "P$2") (pinfunction "P$2_P$2") (pintype "bidirectional"))
    )
    (net (code "59") (name "unconnected-(SW1-PadP$4)") (class "Default")
      (node (ref "SW1") (pin "P$4") (pinfunction "P$4_P$4") (pintype "bidirectional"))
    )
  )
)
